# QCopterFC_CAMSPI_Sch.net
KiCad netlist of a schematic drawn in Altium Designer
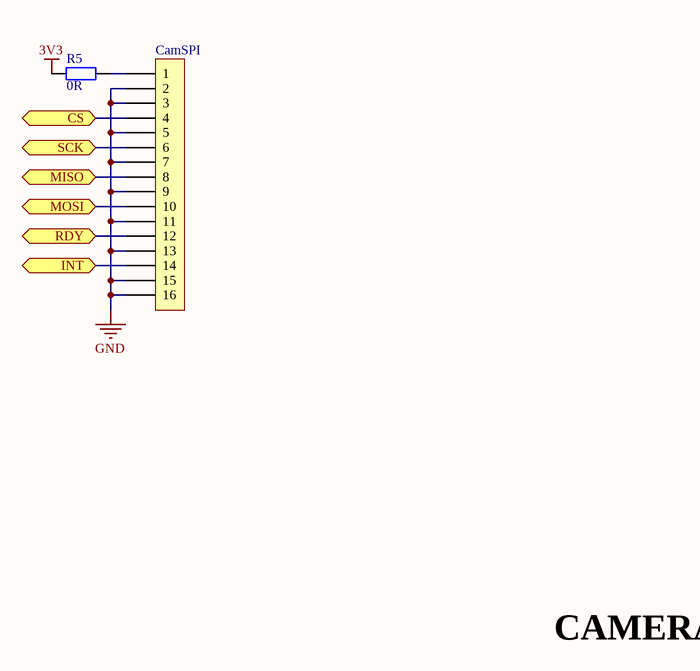
[diagram p0: QCopterFC_CAMSPI_Sch.SchDoc]

(export (version "E")
  (design (tool "Eeschema 10.0.6"))
  (components
    (comp (ref "CamSPI")
      (value "FFC_0.5_16")
      (footprint "PCB_Connector:FFC_0.5_16")
      (description "FFC")
      (libsource (lib "SCH_Connector") (part "FFC_0.5_16"))
    )
    (comp (ref "R5")
      (value "0R")
      (footprint "PCB_Passive:RES_0603")
      (description "Resistor")
      (fields (field (name "Comment") "Res_0603"))
      (libsource (lib "SCH_Passive") (part "Res_0603"))
    )
  )
  (nets
    (net (code "1") (name "/CS") (class "Default")
      (node (ref "CamSPI") (pin "4") (pinfunction "4_4") (pintype "passive"))
    )
    (net (code "2") (name "/INT") (class "Default")
      (node (ref "CamSPI") (pin "14") (pinfunction "14_14") (pintype "passive"))
    )
    (net (code "3") (name "/MISO") (class "Default")
      (node (ref "CamSPI") (pin "8") (pinfunction "8_8") (pintype "passive"))
    )
    (net (code "4") (name "/MOSI") (class "Default")
      (node (ref "CamSPI") (pin "10") (pinfunction "10_10") (pintype "passive"))
    )
    (net (code "5") (name "/RDY") (class "Default")
      (node (ref "CamSPI") (pin "12") (pinfunction "12_12") (pintype "passive"))
    )
    (net (code "6") (name "/SCK") (class "Default")
      (node (ref "CamSPI") (pin "6") (pinfunction "6_6") (pintype "passive"))
    )
    (net (code "7") (name "3V3") (class "Default")
      (node (ref "R5") (pin "1") (pinfunction "1_1") (pintype "passive"))
    )
    (net (code "8") (name "GND") (class "Default")
      (node (ref "CamSPI") (pin "11") (pinfunction "11_11") (pintype "passive"))
      (node (ref "CamSPI") (pin "13") (pinfunction "13_13") (pintype "passive"))
      (node (ref "CamSPI") (pin "15") (pinfunction "15_15") (pintype "passive"))
      (node (ref "CamSPI") (pin "16") (pinfunction "16_16") (pintype "passive"))
      (node (ref "CamSPI") (pin "2") (pinfunction "2_2") (pintype "passive"))
      (node (ref "CamSPI") (pin "3") (pinfunction "3_3") (pintype "passive"))
      (node (ref "CamSPI") (pin "5") (pinfunction "5_5") (pintype "passive"))
      (node (ref "CamSPI") (pin "7") (pinfunction "7_7") (pintype "passive"))
      (node (ref "CamSPI") (pin "9") (pinfunction "9_9") (pintype "passive"))
    )
    (net (code "9") (name "Net-(CamSPI-Pad1)") (class "Default")
      (node (ref "CamSPI") (pin "1") (pinfunction "1_1") (pintype "passive"))
      (node (ref "R5") (pin "2") (pinfunction "2_2") (pintype "passive"))
    )
  )
)
